# IMU.net
KiCad netlist of a schematic drawn in Altium Designer
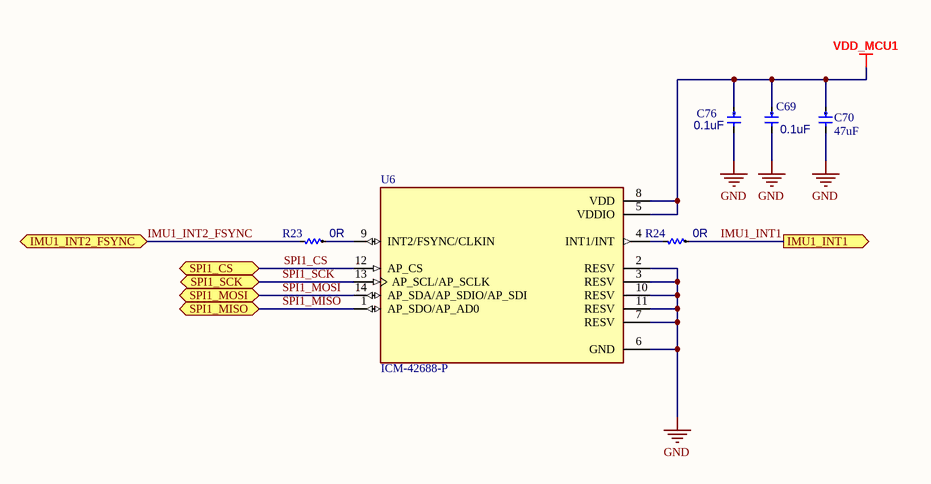
[diagram p0: IMU.SchDoc]

(export (version "E")
  (design (tool "Eeschema 10.0.6"))
  (components
    (comp (ref "C69")
      (value "0.1uF")
      (footprint "CAP0402")
      (description "Cap 0.1uF 50V 0402")
      (fields (field (name "MP") "CC0402KRX5R9BB104") (field (name "TOLERANCE") "10%"))
      (libsource (lib "RTR (1)") (part "CAP0402 0.1uF 50V"))
    )
    (comp (ref "C70")
      (value "CL21A476MQYNNNE")
      (footprint "CAP0805")
      (description "CAP CER 47UF 6.3V X5R 0805")
      (fields (field (name "TOLERANCE") "20%") (field (name "CAPACITANCE") "47uF"))
      (libsource (lib "rtr") (part "885012107014"))
    )
    (comp (ref "C76")
      (value "0.1uF")
      (footprint "CAP0402")
      (description "Cap 0.1uF 50V 0402")
      (fields (field (name "MP") "CC0402KRX5R9BB104") (field (name "TOLERANCE") "10%"))
      (libsource (lib "RTR (1)") (part "CAP0402 0.1uF 50V"))
    )
    (comp (ref "R23")
      (value "0R")
      (footprint "RES0402")
      (description "RES 0R 0402")
      (fields (field (name "MP") "RC0402JR-070RL") (field (name "TOLERANCE") "5%"))
      (libsource (lib "RTR (1)") (part "RES0402 0R"))
    )
    (comp (ref "R24")
      (value "0R")
      (footprint "RES0402")
      (description "RES 0R 0402")
      (fields (field (name "MP") "RC0402JR-070RL") (field (name "TOLERANCE") "5%"))
      (libsource (lib "RTR (1)") (part "RES0402 0R"))
    )
    (comp (ref "U6")
      (value "ICM-42688-P")
      (footprint "IMU42688")
      (description "Accelerometer, Gyroscope, 6 Axis Sensor Output")
      (libsource (lib "DRV8312DDW") (part "ICM-42688-P"))
    )
  )
  (nets
    (net (code "1") (name "/IMU1_INT1") (class "Default")
      (node (ref "R24") (pin "2") (pinfunction "2_2") (pintype "passive"))
    )
    (net (code "2") (name "/IMU1_INT2_FSYNC") (class "Default")
      (node (ref "R23") (pin "1") (pinfunction "1_1") (pintype "passive"))
    )
    (net (code "3") (name "/SPI1_CS") (class "Default")
      (node (ref "U6") (pin "12") (pinfunction "AP_CS_12") (pintype "input"))
    )
    (net (code "4") (name "/SPI1_MISO") (class "Default")
      (node (ref "U6") (pin "1") (pinfunction "AP_SDO/AP_AD0_1") (pintype "bidirectional"))
    )
    (net (code "5") (name "/SPI1_MOSI") (class "Default")
      (node (ref "U6") (pin "14") (pinfunction "AP_SDA/AP_SDIO/AP_SDI_14") (pintype "bidirectional"))
    )
    (net (code "6") (name "/SPI1_SCK") (class "Default")
      (node (ref "U6") (pin "13") (pinfunction "AP_SCL/AP_SCLK_13") (pintype "input"))
    )
    (net (code "7") (name "GND") (class "Default")
      (node (ref "C69") (pin "2") (pinfunction "2_2") (pintype "passive"))
      (node (ref "C70") (pin "2") (pinfunction "2_2") (pintype "passive"))
      (node (ref "C76") (pin "2") (pinfunction "2_2") (pintype "passive"))
      (node (ref "U6") (pin "10") (pinfunction "RESV_10") (pintype "passive"))
      (node (ref "U6") (pin "11") (pinfunction "RESV_11") (pintype "passive"))
      (node (ref "U6") (pin "2") (pinfunction "RESV_2") (pintype "passive"))
      (node (ref "U6") (pin "3") (pinfunction "RESV_3") (pintype "passive"))
      (node (ref "U6") (pin "6") (pinfunction "GND_6") (pintype "power_in"))
      (node (ref "U6") (pin "7") (pinfunction "RESV_7") (pintype "passive"))
    )
    (net (code "8") (name "Net-(U6-INT1{slash}INT)") (class "Default")
      (node (ref "R24") (pin "1") (pinfunction "1_1") (pintype "passive"))
      (node (ref "U6") (pin "4") (pinfunction "INT1/INT_4") (pintype "output"))
    )
    (net (code "9") (name "Net-(U6-INT2{slash}FSYNC{slash}CLKIN)") (class "Default")
      (node (ref "R23") (pin "2") (pinfunction "2_2") (pintype "passive"))
      (node (ref "U6") (pin "9") (pinfunction "INT2/FSYNC/CLKIN_9") (pintype "bidirectional"))
    )
    (net (code "10") (name "VDD_MCU1") (class "Default")
      (node (ref "C69") (pin "1") (pinfunction "1_1") (pintype "passive"))
      (node (ref "C70") (pin "1") (pinfunction "1_1") (pintype "passive"))
      (node (ref "C76") (pin "1") (pinfunction "1_1") (pintype "passive"))
      (node (ref "U6") (pin "5") (pinfunction "VDDIO_5") (pintype "power_in"))
      (node (ref "U6") (pin "8") (pinfunction "VDD_8") (pintype "power_in"))
    )
  )
)
